# arduino_adapter.net
KiCad netlist of a schematic drawn in EAGLE
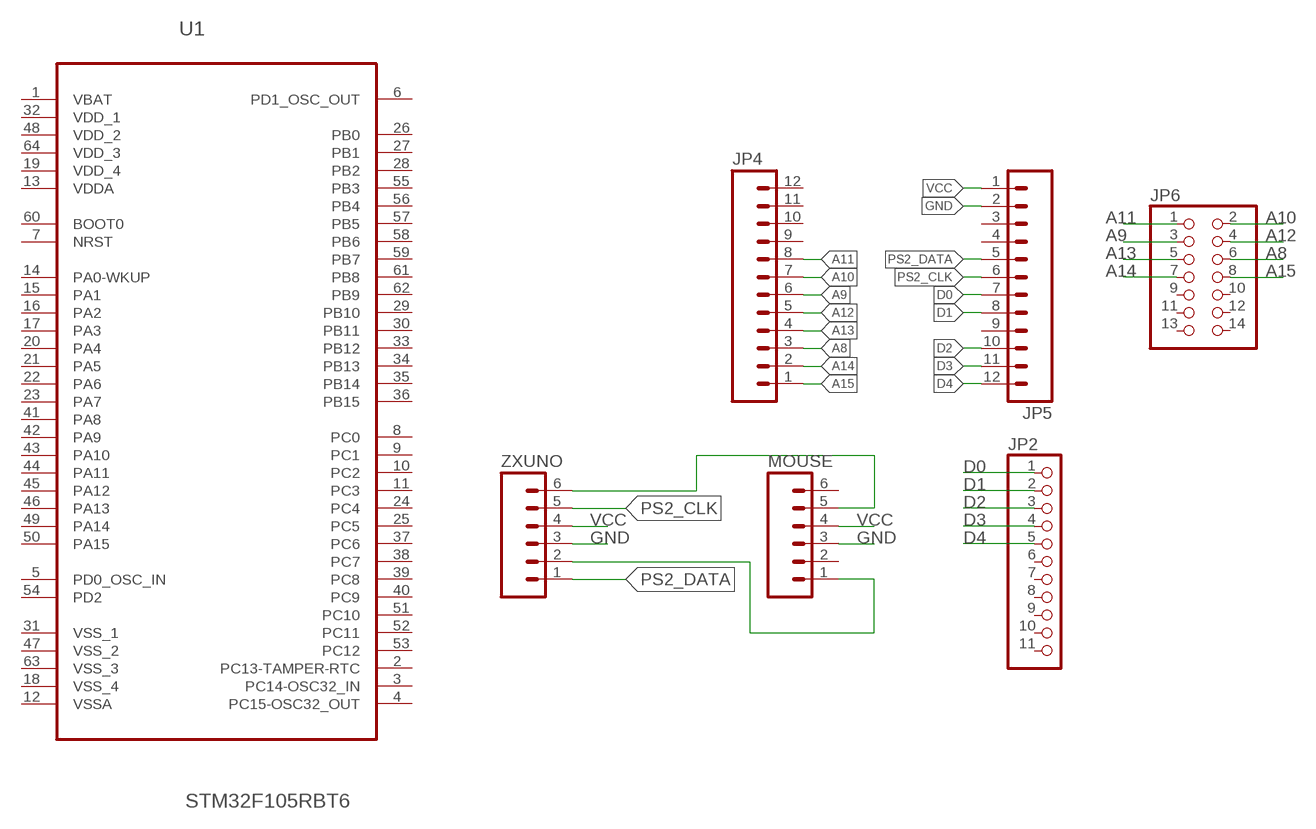
[diagram p0: schematic, sheet 1]

(export (version "E")
  (design (tool "Eeschema 10.0.6"))
  (components
    (comp (ref "JP2")
      (value "PINHD-1X11")
      (footprint "eagle-import:1X11")
      (libsource (lib "eagle-import") (part "PINHD-1X11"))
    )
    (comp (ref "JP4")
      (value "M12PTH")
      (footprint "eagle-import:1X12")
      (libsource (lib "eagle-import") (part "M12PTH"))
    )
    (comp (ref "JP5")
      (value "M12PTH")
      (footprint "eagle-import:1X12")
      (libsource (lib "eagle-import") (part "M12PTH"))
    )
    (comp (ref "JP6")
      (value "PINHD-2X7")
      (footprint "eagle-import:2X07")
      (libsource (lib "eagle-import") (part "PINHD-2X7"))
    )
    (comp (ref "MOUSE")
      (value "DINC_MIN_TM_6_1")
      (footprint "eagle-import:DINC_MIN_TM_6_1PRIMARY")
      (libsource (lib "eagle-import") (part "DINC_MIN_TM_6_1"))
    )
    (comp (ref "U1")
      (value "STM32F105RBT6")
      (footprint "eagle-import:QFP50P1200X1200X160-64N")
      (libsource (lib "eagle-import") (part "STM32F105RBT6"))
    )
    (comp (ref "ZXUNO")
      (value "DINC_MIN_TM_6_1")
      (footprint "eagle-import:DINC_MIN_TM_6_1PRIMARY")
      (libsource (lib "eagle-import") (part "DINC_MIN_TM_6_1"))
    )
  )
  (nets
    (net (code "1") (name "/VBAT") (class "Default")
      (node (ref "U1") (pin "1") (pinfunction "VBAT_1") (pintype "power_in"))
    )
    (net (code "2") (name "/VDDA") (class "Default")
      (node (ref "U1") (pin "13") (pinfunction "VDDA_13") (pintype "power_in"))
    )
    (net (code "3") (name "/VDD_1") (class "Default")
      (node (ref "U1") (pin "32") (pinfunction "VDD_1_32") (pintype "power_in"))
    )
    (net (code "4") (name "/VDD_2") (class "Default")
      (node (ref "U1") (pin "48") (pinfunction "VDD_2_48") (pintype "power_in"))
    )
    (net (code "5") (name "/VDD_3") (class "Default")
      (node (ref "U1") (pin "64") (pinfunction "VDD_3_64") (pintype "power_in"))
    )
    (net (code "6") (name "/VDD_4") (class "Default")
      (node (ref "U1") (pin "19") (pinfunction "VDD_4_19") (pintype "power_in"))
    )
    (net (code "7") (name "/VSSA") (class "Default")
      (node (ref "U1") (pin "12") (pinfunction "VSSA_12") (pintype "power_in"))
    )
    (net (code "8") (name "/VSS_1") (class "Default")
      (node (ref "U1") (pin "31") (pinfunction "VSS_1_31") (pintype "power_in"))
    )
    (net (code "9") (name "/VSS_2") (class "Default")
      (node (ref "U1") (pin "47") (pinfunction "VSS_2_47") (pintype "power_in"))
    )
    (net (code "10") (name "/VSS_3") (class "Default")
      (node (ref "U1") (pin "63") (pinfunction "VSS_3_63") (pintype "power_in"))
    )
    (net (code "11") (name "/VSS_4") (class "Default")
      (node (ref "U1") (pin "18") (pinfunction "VSS_4_18") (pintype "power_in"))
    )
    (net (code "12") (name "A8") (class "Default")
      (node (ref "JP4") (pin "3") (pinfunction "3_3") (pintype "passive"))
      (node (ref "JP6") (pin "6") (pinfunction "6_6") (pintype "passive"))
    )
    (net (code "13") (name "A9") (class "Default")
      (node (ref "JP4") (pin "6") (pinfunction "6_6") (pintype "passive"))
      (node (ref "JP6") (pin "3") (pinfunction "3_3") (pintype "passive"))
    )
    (net (code "14") (name "A10") (class "Default")
      (node (ref "JP4") (pin "7") (pinfunction "7_7") (pintype "passive"))
      (node (ref "JP6") (pin "2") (pinfunction "2_2") (pintype "passive"))
    )
    (net (code "15") (name "A11") (class "Default")
      (node (ref "JP4") (pin "8") (pinfunction "8_8") (pintype "passive"))
      (node (ref "JP6") (pin "1") (pinfunction "1_1") (pintype "passive"))
    )
    (net (code "16") (name "A12") (class "Default")
      (node (ref "JP4") (pin "5") (pinfunction "5_5") (pintype "passive"))
      (node (ref "JP6") (pin "4") (pinfunction "4_4") (pintype "passive"))
    )
    (net (code "17") (name "A13") (class "Default")
      (node (ref "JP4") (pin "4") (pinfunction "4_4") (pintype "passive"))
      (node (ref "JP6") (pin "5") (pinfunction "5_5") (pintype "passive"))
    )
    (net (code "18") (name "A14") (class "Default")
      (node (ref "JP4") (pin "2") (pinfunction "2_2") (pintype "passive"))
      (node (ref "JP6") (pin "7") (pinfunction "7_7") (pintype "passive"))
    )
    (net (code "19") (name "A15") (class "Default")
      (node (ref "JP4") (pin "1") (pinfunction "1_1") (pintype "passive"))
      (node (ref "JP6") (pin "8") (pinfunction "8_8") (pintype "passive"))
    )
    (net (code "20") (name "D0") (class "Default")
      (node (ref "JP2") (pin "1") (pinfunction "1_1") (pintype "passive"))
      (node (ref "JP5") (pin "7") (pinfunction "7_7") (pintype "passive"))
    )
    (net (code "21") (name "D1") (class "Default")
      (node (ref "JP2") (pin "2") (pinfunction "2_2") (pintype "passive"))
      (node (ref "JP5") (pin "8") (pinfunction "8_8") (pintype "passive"))
    )
    (net (code "22") (name "D2") (class "Default")
      (node (ref "JP2") (pin "3") (pinfunction "3_3") (pintype "passive"))
      (node (ref "JP5") (pin "10") (pinfunction "10_10") (pintype "passive"))
    )
    (net (code "23") (name "D3") (class "Default")
      (node (ref "JP2") (pin "4") (pinfunction "4_4") (pintype "passive"))
      (node (ref "JP5") (pin "11") (pinfunction "11_11") (pintype "passive"))
    )
    (net (code "24") (name "D4") (class "Default")
      (node (ref "JP2") (pin "5") (pinfunction "5_5") (pintype "passive"))
      (node (ref "JP5") (pin "12") (pinfunction "12_12") (pintype "passive"))
    )
    (net (code "25") (name "GND") (class "Default")
      (node (ref "JP5") (pin "2") (pinfunction "2_2") (pintype "passive"))
      (node (ref "MOUSE") (pin "3") (pinfunction "3_3") (pintype "passive"))
      (node (ref "ZXUNO") (pin "3") (pinfunction "3_3") (pintype "passive"))
    )
    (net (code "26") (name "Net-(MOUSE-Pad1)") (class "Default")
      (node (ref "MOUSE") (pin "1") (pinfunction "1_1") (pintype "passive"))
      (node (ref "ZXUNO") (pin "2") (pinfunction "2_2") (pintype "passive"))
    )
    (net (code "27") (name "Net-(MOUSE-Pad5)") (class "Default")
      (node (ref "MOUSE") (pin "5") (pinfunction "5_5") (pintype "passive"))
      (node (ref "ZXUNO") (pin "6") (pinfunction "6_6") (pintype "passive"))
    )
    (net (code "28") (name "PS2_CLK") (class "Default")
      (node (ref "JP5") (pin "6") (pinfunction "6_6") (pintype "passive"))
      (node (ref "ZXUNO") (pin "5") (pinfunction "5_5") (pintype "passive"))
    )
    (net (code "29") (name "PS2_DATA") (class "Default")
      (node (ref "JP5") (pin "5") (pinfunction "5_5") (pintype "passive"))
      (node (ref "ZXUNO") (pin "1") (pinfunction "1_1") (pintype "passive"))
    )
    (net (code "30") (name "VCC") (class "Default")
      (node (ref "JP5") (pin "1") (pinfunction "1_1") (pintype "passive"))
      (node (ref "MOUSE") (pin "4") (pinfunction "4_4") (pintype "passive"))
      (node (ref "ZXUNO") (pin "4") (pinfunction "4_4") (pintype "passive"))
    )
    (net (code "31") (name "unconnected-(JP2-Pad6)") (class "Default")
      (node (ref "JP2") (pin "6") (pinfunction "6_6") (pintype "passive"))
    )
    (net (code "32") (name "unconnected-(JP2-Pad7)") (class "Default")
      (node (ref "JP2") (pin "7") (pinfunction "7_7") (pintype "passive"))
    )
    (net (code "33") (name "unconnected-(JP2-Pad8)") (class "Default")
      (node (ref "JP2") (pin "8") (pinfunction "8_8") (pintype "passive"))
    )
    (net (code "34") (name "unconnected-(JP2-Pad9)") (class "Default")
      (node (ref "JP2") (pin "9") (pinfunction "9_9") (pintype "passive"))
    )
    (net (code "35") (name "unconnected-(JP2-Pad10)") (class "Default")
      (node (ref "JP2") (pin "10") (pinfunction "10_10") (pintype "passive"))
    )
    (net (code "36") (name "unconnected-(JP2-Pad11)") (class "Default")
      (node (ref "JP2") (pin "11") (pinfunction "11_11") (pintype "passive"))
    )
    (net (code "37") (name "unconnected-(JP4-Pad9)") (class "Default")
      (node (ref "JP4") (pin "9") (pinfunction "9_9") (pintype "passive"))
    )
    (net (code "38") (name "unconnected-(JP4-Pad10)") (class "Default")
      (node (ref "JP4") (pin "10") (pinfunction "10_10") (pintype "passive"))
    )
    (net (code "39") (name "unconnected-(JP4-Pad11)") (class "Default")
      (node (ref "JP4") (pin "11") (pinfunction "11_11") (pintype "passive"))
    )
    (net (code "40") (name "unconnected-(JP4-Pad12)") (class "Default")
      (node (ref "JP4") (pin "12") (pinfunction "12_12") (pintype "passive"))
    )
    (net (code "41") (name "unconnected-(JP5-Pad3)") (class "Default")
      (node (ref "JP5") (pin "3") (pinfunction "3_3") (pintype "passive"))
    )
    (net (code "42") (name "unconnected-(JP5-Pad4)") (class "Default")
      (node (ref "JP5") (pin "4") (pinfunction "4_4") (pintype "passive"))
    )
    (net (code "43") (name "unconnected-(JP5-Pad9)") (class "Default")
      (node (ref "JP5") (pin "9") (pinfunction "9_9") (pintype "passive"))
    )
    (net (code "44") (name "unconnected-(JP6-Pad9)") (class "Default")
      (node (ref "JP6") (pin "9") (pinfunction "9_9") (pintype "passive"))
    )
    (net (code "45") (name "unconnected-(JP6-Pad10)") (class "Default")
      (node (ref "JP6") (pin "10") (pinfunction "10_10") (pintype "passive"))
    )
    (net (code "46") (name "unconnected-(JP6-Pad11)") (class "Default")
      (node (ref "JP6") (pin "11") (pinfunction "11_11") (pintype "passive"))
    )
    (net (code "47") (name "unconnected-(JP6-Pad12)") (class "Default")
      (node (ref "JP6") (pin "12") (pinfunction "12_12") (pintype "passive"))
    )
    (net (code "48") (name "unconnected-(JP6-Pad13)") (class "Default")
      (node (ref "JP6") (pin "13") (pinfunction "13_13") (pintype "passive"))
    )
    (net (code "49") (name "unconnected-(JP6-Pad14)") (class "Default")
      (node (ref "JP6") (pin "14") (pinfunction "14_14") (pintype "passive"))
    )
    (net (code "50") (name "unconnected-(MOUSE-Pad2)") (class "Default")
      (node (ref "MOUSE") (pin "2") (pinfunction "2_2") (pintype "passive"))
    )
    (net (code "51") (name "unconnected-(MOUSE-Pad6)") (class "Default")
      (node (ref "MOUSE") (pin "6") (pinfunction "6_6") (pintype "passive"))
    )
    (net (code "52") (name "unconnected-(U1-BOOT0-Pad60)") (class "Default")
      (node (ref "U1") (pin "60") (pinfunction "BOOT0_60") (pintype "input"))
    )
    (net (code "53") (name "unconnected-(U1-NRST-Pad7)") (class "Default")
      (node (ref "U1") (pin "7") (pinfunction "NRST_7") (pintype "bidirectional"))
    )
    (net (code "54") (name "unconnected-(U1-PA0-WKUP-Pad14)") (class "Default")
      (node (ref "U1") (pin "14") (pinfunction "PA0-WKUP_14") (pintype "bidirectional"))
    )
    (net (code "55") (name "unconnected-(U1-PA1-Pad15)") (class "Default")
      (node (ref "U1") (pin "15") (pinfunction "PA1_15") (pintype "bidirectional"))
    )
    (net (code "56") (name "unconnected-(U1-PA2-Pad16)") (class "Default")
      (node (ref "U1") (pin "16") (pinfunction "PA2_16") (pintype "bidirectional"))
    )
    (net (code "57") (name "unconnected-(U1-PA3-Pad17)") (class "Default")
      (node (ref "U1") (pin "17") (pinfunction "PA3_17") (pintype "bidirectional"))
    )
    (net (code "58") (name "unconnected-(U1-PA4-Pad20)") (class "Default")
      (node (ref "U1") (pin "20") (pinfunction "PA4_20") (pintype "bidirectional"))
    )
    (net (code "59") (name "unconnected-(U1-PA5-Pad21)") (class "Default")
      (node (ref "U1") (pin "21") (pinfunction "PA5_21") (pintype "bidirectional"))
    )
    (net (code "60") (name "unconnected-(U1-PA6-Pad22)") (class "Default")
      (node (ref "U1") (pin "22") (pinfunction "PA6_22") (pintype "bidirectional"))
    )
    (net (code "61") (name "unconnected-(U1-PA7-Pad23)") (class "Default")
      (node (ref "U1") (pin "23") (pinfunction "PA7_23") (pintype "bidirectional"))
    )
    (net (code "62") (name "unconnected-(U1-PA8-Pad41)") (class "Default")
      (node (ref "U1") (pin "41") (pinfunction "PA8_41") (pintype "bidirectional"))
    )
    (net (code "63") (name "unconnected-(U1-PA9-Pad42)") (class "Default")
      (node (ref "U1") (pin "42") (pinfunction "PA9_42") (pintype "bidirectional"))
    )
    (net (code "64") (name "unconnected-(U1-PA10-Pad43)") (class "Default")
      (node (ref "U1") (pin "43") (pinfunction "PA10_43") (pintype "bidirectional"))
    )
    (net (code "65") (name "unconnected-(U1-PA11-Pad44)") (class "Default")
      (node (ref "U1") (pin "44") (pinfunction "PA11_44") (pintype "bidirectional"))
    )
    (net (code "66") (name "unconnected-(U1-PA12-Pad45)") (class "Default")
      (node (ref "U1") (pin "45") (pinfunction "PA12_45") (pintype "bidirectional"))
    )
    (net (code "67") (name "unconnected-(U1-PA13-Pad46)") (class "Default")
      (node (ref "U1") (pin "46") (pinfunction "PA13_46") (pintype "bidirectional"))
    )
    (net (code "68") (name "unconnected-(U1-PA14-Pad49)") (class "Default")
      (node (ref "U1") (pin "49") (pinfunction "PA14_49") (pintype "bidirectional"))
    )
    (net (code "69") (name "unconnected-(U1-PA15-Pad50)") (class "Default")
      (node (ref "U1") (pin "50") (pinfunction "PA15_50") (pintype "bidirectional"))
    )
    (net (code "70") (name "unconnected-(U1-PB0-Pad26)") (class "Default")
      (node (ref "U1") (pin "26") (pinfunction "PB0_26") (pintype "bidirectional"))
    )
    (net (code "71") (name "unconnected-(U1-PB1-Pad27)") (class "Default")
      (node (ref "U1") (pin "27") (pinfunction "PB1_27") (pintype "bidirectional"))
    )
    (net (code "72") (name "unconnected-(U1-PB2-Pad28)") (class "Default")
      (node (ref "U1") (pin "28") (pinfunction "PB2_28") (pintype "bidirectional"))
    )
    (net (code "73") (name "unconnected-(U1-PB3-Pad55)") (class "Default")
      (node (ref "U1") (pin "55") (pinfunction "PB3_55") (pintype "bidirectional"))
    )
    (net (code "74") (name "unconnected-(U1-PB4-Pad56)") (class "Default")
      (node (ref "U1") (pin "56") (pinfunction "PB4_56") (pintype "bidirectional"))
    )
    (net (code "75") (name "unconnected-(U1-PB5-Pad57)") (class "Default")
      (node (ref "U1") (pin "57") (pinfunction "PB5_57") (pintype "bidirectional"))
    )
    (net (code "76") (name "unconnected-(U1-PB6-Pad58)") (class "Default")
      (node (ref "U1") (pin "58") (pinfunction "PB6_58") (pintype "bidirectional"))
    )
    (net (code "77") (name "unconnected-(U1-PB7-Pad59)") (class "Default")
      (node (ref "U1") (pin "59") (pinfunction "PB7_59") (pintype "bidirectional"))
    )
    (net (code "78") (name "unconnected-(U1-PB8-Pad61)") (class "Default")
      (node (ref "U1") (pin "61") (pinfunction "PB8_61") (pintype "bidirectional"))
    )
    (net (code "79") (name "unconnected-(U1-PB9-Pad62)") (class "Default")
      (node (ref "U1") (pin "62") (pinfunction "PB9_62") (pintype "bidirectional"))
    )
    (net (code "80") (name "unconnected-(U1-PB10-Pad29)") (class "Default")
      (node (ref "U1") (pin "29") (pinfunction "PB10_29") (pintype "bidirectional"))
    )
    (net (code "81") (name "unconnected-(U1-PB11-Pad30)") (class "Default")
      (node (ref "U1") (pin "30") (pinfunction "PB11_30") (pintype "bidirectional"))
    )
    (net (code "82") (name "unconnected-(U1-PB12-Pad33)") (class "Default")
      (node (ref "U1") (pin "33") (pinfunction "PB12_33") (pintype "bidirectional"))
    )
    (net (code "83") (name "unconnected-(U1-PB13-Pad34)") (class "Default")
      (node (ref "U1") (pin "34") (pinfunction "PB13_34") (pintype "bidirectional"))
    )
    (net (code "84") (name "unconnected-(U1-PB14-Pad35)") (class "Default")
      (node (ref "U1") (pin "35") (pinfunction "PB14_35") (pintype "bidirectional"))
    )
    (net (code "85") (name "unconnected-(U1-PB15-Pad36)") (class "Default")
      (node (ref "U1") (pin "36") (pinfunction "PB15_36") (pintype "bidirectional"))
    )
    (net (code "86") (name "unconnected-(U1-PC0-Pad8)") (class "Default")
      (node (ref "U1") (pin "8") (pinfunction "PC0_8") (pintype "bidirectional"))
    )
    (net (code "87") (name "unconnected-(U1-PC1-Pad9)") (class "Default")
      (node (ref "U1") (pin "9") (pinfunction "PC1_9") (pintype "bidirectional"))
    )
    (net (code "88") (name "unconnected-(U1-PC2-Pad10)") (class "Default")
      (node (ref "U1") (pin "10") (pinfunction "PC2_10") (pintype "bidirectional"))
    )
    (net (code "89") (name "unconnected-(U1-PC3-Pad11)") (class "Default")
      (node (ref "U1") (pin "11") (pinfunction "PC3_11") (pintype "bidirectional"))
    )
    (net (code "90") (name "unconnected-(U1-PC4-Pad24)") (class "Default")
      (node (ref "U1") (pin "24") (pinfunction "PC4_24") (pintype "bidirectional"))
    )
    (net (code "91") (name "unconnected-(U1-PC5-Pad25)") (class "Default")
      (node (ref "U1") (pin "25") (pinfunction "PC5_25") (pintype "bidirectional"))
    )
    (net (code "92") (name "unconnected-(U1-PC6-Pad37)") (class "Default")
      (node (ref "U1") (pin "37") (pinfunction "PC6_37") (pintype "bidirectional"))
    )
    (net (code "93") (name "unconnected-(U1-PC7-Pad38)") (class "Default")
      (node (ref "U1") (pin "38") (pinfunction "PC7_38") (pintype "bidirectional"))
    )
    (net (code "94") (name "unconnected-(U1-PC8-Pad39)") (class "Default")
      (node (ref "U1") (pin "39") (pinfunction "PC8_39") (pintype "bidirectional"))
    )
    (net (code "95") (name "unconnected-(U1-PC9-Pad40)") (class "Default")
      (node (ref "U1") (pin "40") (pinfunction "PC9_40") (pintype "bidirectional"))
    )
    (net (code "96") (name "unconnected-(U1-PC10-Pad51)") (class "Default")
      (node (ref "U1") (pin "51") (pinfunction "PC10_51") (pintype "bidirectional"))
    )
    (net (code "97") (name "unconnected-(U1-PC11-Pad52)") (class "Default")
      (node (ref "U1") (pin "52") (pinfunction "PC11_52") (pintype "bidirectional"))
    )
    (net (code "98") (name "unconnected-(U1-PC12-Pad53)") (class "Default")
      (node (ref "U1") (pin "53") (pinfunction "PC12_53") (pintype "bidirectional"))
    )
    (net (code "99") (name "unconnected-(U1-PC13-TAMPER-RTC-Pad2)") (class "Default")
      (node (ref "U1") (pin "2") (pinfunction "PC13-TAMPER-RTC_2") (pintype "bidirectional"))
    )
    (net (code "100") (name "unconnected-(U1-PC14-OSC32_IN-Pad3)") (class "Default")
      (node (ref "U1") (pin "3") (pinfunction "PC14-OSC32_IN_3") (pintype "bidirectional"))
    )
    (net (code "101") (name "unconnected-(U1-PC15-OSC32_OUT-Pad4)") (class "Default")
      (node (ref "U1") (pin "4") (pinfunction "PC15-OSC32_OUT_4") (pintype "bidirectional"))
    )
    (net (code "102") (name "unconnected-(U1-PD0_OSC_IN-Pad5)") (class "Default")
      (node (ref "U1") (pin "5") (pinfunction "PD0_OSC_IN_5") (pintype "bidirectional"))
    )
    (net (code "103") (name "unconnected-(U1-PD1_OSC_OUT-Pad6)") (class "Default")
      (node (ref "U1") (pin "6") (pinfunction "PD1_OSC_OUT_6") (pintype "bidirectional"))
    )
    (net (code "104") (name "unconnected-(U1-PD2-Pad54)") (class "Default")
      (node (ref "U1") (pin "54") (pinfunction "PD2_54") (pintype "bidirectional"))
    )
  )
)
